# MegaShieldDB.net
KiCad netlist of a schematic drawn in EAGLE
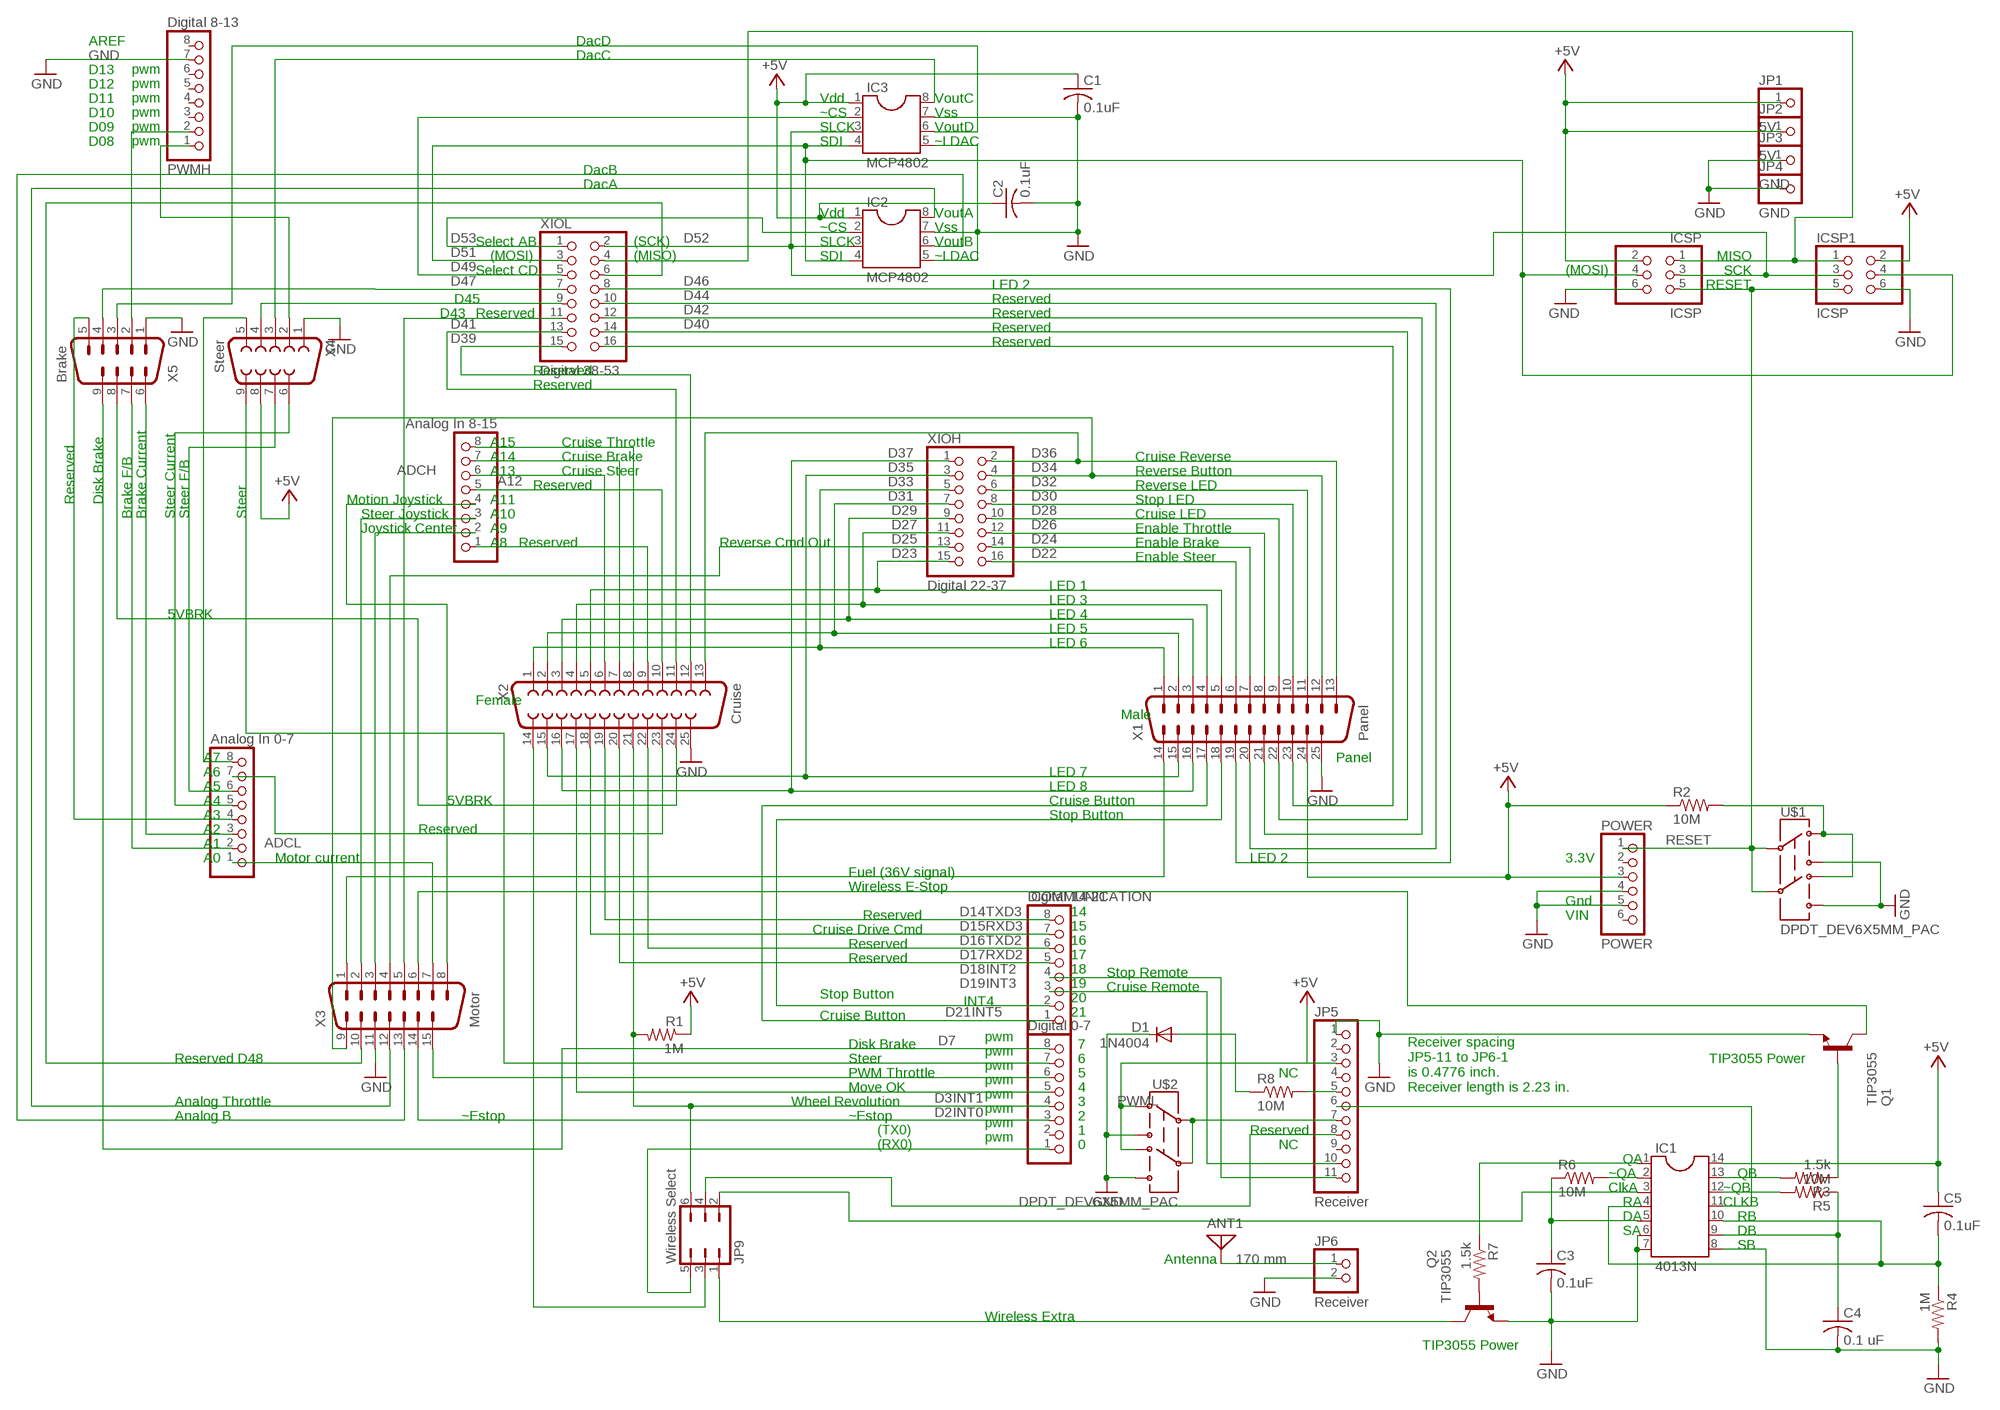
[diagram p0: schematic, sheet 1]

(export (version "E")
  (design (tool "Eeschema 10.0.6"))
  (components
    (comp (ref "ADCH")
      (value "Analog In 8-15")
      (footprint "eagle-import:1X08")
      (libsource (lib "eagle-import") (part "PINHD-1X8"))
    )
    (comp (ref "ADCL")
      (value "Analog In 0-7")
      (footprint "eagle-import:1X08")
      (libsource (lib "eagle-import") (part "PINHD-1X8"))
    )
    (comp (ref "ANT1")
      (value "170 mm")
      (footprint "eagle-import:PAD-01")
      (libsource (lib "eagle-import") (part "ANTENNA"))
    )
    (comp (ref "C1")
      (value "0.1uF")
      (footprint "eagle-import:C025-025X050")
      (libsource (lib "eagle-import") (part "C-US025-025X050"))
    )
    (comp (ref "C2")
      (value "0.1uF")
      (footprint "eagle-import:C025-025X050")
      (libsource (lib "eagle-import") (part "C-US025-025X050"))
    )
    (comp (ref "C3")
      (value "0.1uF")
      (footprint "eagle-import:C025-025X050")
      (libsource (lib "eagle-import") (part "C-US025-025X050"))
    )
    (comp (ref "C4")
      (value "0.1 uF")
      (footprint "eagle-import:C025-025X050")
      (libsource (lib "eagle-import") (part "C-US025-025X050"))
    )
    (comp (ref "C5")
      (value "0.1uF")
      (footprint "eagle-import:C025-025X050")
      (libsource (lib "eagle-import") (part "C-US025-025X050"))
    )
    (comp (ref "COMMUNICATION")
      (value "Digital 14-21")
      (footprint "eagle-import:1X08")
      (libsource (lib "eagle-import") (part "PINHD-1X8"))
    )
    (comp (ref "D1")
      (value "1N4004")
      (footprint "eagle-import:DO41-10")
      (libsource (lib "eagle-import") (part "1N4004"))
    )
    (comp (ref "IC1")
      (value "4013N")
      (footprint "eagle-import:DIL14")
      (libsource (lib "eagle-import") (part "DIL14"))
    )
    (comp (ref "IC2")
      (value "MCP4802")
      (footprint "eagle-import:DIL08")
      (libsource (lib "eagle-import") (part "DIL8"))
    )
    (comp (ref "IC3")
      (value "MCP4802")
      (footprint "eagle-import:DIL08")
      (libsource (lib "eagle-import") (part "DIL8"))
    )
    (comp (ref "ICSP")
      (value "ICSP")
      (footprint "eagle-import:2X03")
      (libsource (lib "eagle-import") (part "PINHD-2X3"))
    )
    (comp (ref "ICSP1")
      (value "ICSP")
      (footprint "eagle-import:2X03")
      (libsource (lib "eagle-import") (part "PINHD-2X3"))
    )
    (comp (ref "JP1")
      (value "5V")
      (footprint "eagle-import:1X01")
      (libsource (lib "eagle-import") (part "PINHD-1X1"))
    )
    (comp (ref "JP2")
      (value "5V")
      (footprint "eagle-import:1X01")
      (libsource (lib "eagle-import") (part "PINHD-1X1"))
    )
    (comp (ref "JP3")
      (value "GND")
      (footprint "eagle-import:1X01")
      (libsource (lib "eagle-import") (part "PINHD-1X1"))
    )
    (comp (ref "JP4")
      (value "GND")
      (footprint "eagle-import:1X01")
      (libsource (lib "eagle-import") (part "PINHD-1X1"))
    )
    (comp (ref "JP5")
      (value "Receiver")
      (footprint "eagle-import:1X11")
      (libsource (lib "eagle-import") (part "PINHD-1X11"))
    )
    (comp (ref "JP6")
      (value "Receiver")
      (footprint "eagle-import:1X02")
      (libsource (lib "eagle-import") (part "PINHD-1X2"))
    )
    (comp (ref "JP9")
      (value "Wireless Select")
      (footprint "eagle-import:JP3Q")
      (libsource (lib "eagle-import") (part "JP3Q"))
    )
    (comp (ref "POWER")
      (value "POWER")
      (footprint "eagle-import:1X06")
      (libsource (lib "eagle-import") (part "PINHD-1X6"))
    )
    (comp (ref "PWMH")
      (value "Digital 8-13")
      (footprint "eagle-import:1X08")
      (libsource (lib "eagle-import") (part "PINHD-1X8"))
    )
    (comp (ref "PWML")
      (value "Digital 0-7")
      (footprint "eagle-import:1X08")
      (libsource (lib "eagle-import") (part "PINHD-1X8"))
    )
    (comp (ref "Q1")
      (value "TIP3055")
      (footprint "eagle-import:TO220")
      (libsource (lib "eagle-import") (part "BD239"))
    )
    (comp (ref "Q2")
      (value "TIP3055")
      (footprint "eagle-import:TO220")
      (libsource (lib "eagle-import") (part "BD239"))
    )
    (comp (ref "R1")
      (value "1M")
      (footprint "eagle-import:0204_5")
      (libsource (lib "eagle-import") (part "R-US_0204/5"))
    )
    (comp (ref "R2")
      (value "10M")
      (footprint "eagle-import:0204_5")
      (libsource (lib "eagle-import") (part "R-US_0204/5"))
    )
    (comp (ref "R3")
      (value "1.5k")
      (footprint "eagle-import:0204_5")
      (libsource (lib "eagle-import") (part "R-US_0204/5"))
    )
    (comp (ref "R4")
      (value "1M")
      (footprint "eagle-import:0204_5")
      (libsource (lib "eagle-import") (part "R-US_0204/5"))
    )
    (comp (ref "R5")
      (value "10M")
      (footprint "eagle-import:0204_5")
      (libsource (lib "eagle-import") (part "R-US_0204/5"))
    )
    (comp (ref "R6")
      (value "10M")
      (footprint "eagle-import:0204_5")
      (libsource (lib "eagle-import") (part "R-US_0204/5"))
    )
    (comp (ref "R7")
      (value "1.5k")
      (footprint "eagle-import:0204_5")
      (libsource (lib "eagle-import") (part "R-US_0204/5"))
    )
    (comp (ref "R8")
      (value "10M")
      (footprint "eagle-import:0204_5")
      (libsource (lib "eagle-import") (part "R-US_0204/5"))
    )
    (comp (ref "U$1")
      (value "DPDT_DEV6X5MM_PAC")
      (footprint "eagle-import:NEWSWITCH2_PAC")
      (libsource (lib "eagle-import") (part "DPDT_DEV6X5MM_PAC"))
    )
    (comp (ref "U$2")
      (value "DPDT_DEV6X5MM_PAC")
      (footprint "eagle-import:NEWSWITCH2_PAC")
      (libsource (lib "eagle-import") (part "DPDT_DEV6X5MM_PAC"))
    )
    (comp (ref "X1")
      (value "Panel")
      (footprint "eagle-import:M25-HD-20")
      (libsource (lib "eagle-import") (part "M25-HD-20"))
    )
    (comp (ref "X2")
      (value "Cruise")
      (footprint "eagle-import:F25H")
      (libsource (lib "eagle-import") (part "F25H"))
    )
    (comp (ref "X3")
      (value "Motor")
      (footprint "eagle-import:182-015-MALE")
      (libsource (lib "eagle-import") (part "M15-182"))
    )
    (comp (ref "X4")
      (value "Steer")
      (footprint "eagle-import:F09H")
      (libsource (lib "eagle-import") (part "F09H"))
    )
    (comp (ref "X5")
      (value "Brake")
      (footprint "eagle-import:182-009-MALE")
      (libsource (lib "eagle-import") (part "M09-182"))
    )
    (comp (ref "XIOH")
      (value "Digital 22-37")
      (footprint "eagle-import:2X08")
      (libsource (lib "eagle-import") (part "PINHD-2X8"))
    )
    (comp (ref "XIOL")
      (value "Digital 38-53")
      (footprint "eagle-import:2X08")
      (libsource (lib "eagle-import") (part "PINHD-2X8"))
    )
  )
  (nets
    (net (code "1") (name "+5V") (class "Default")
      (node (ref "C1") (pin "1") (pinfunction "1_1") (pintype "passive"))
      (node (ref "C2") (pin "1") (pinfunction "1_1") (pintype "passive"))
      (node (ref "C5") (pin "1") (pinfunction "1_1") (pintype "passive"))
      (node (ref "IC1") (pin "14") (pinfunction "14_14") (pintype "passive"))
      (node (ref "IC2") (pin "1") (pinfunction "1_1") (pintype "passive"))
      (node (ref "IC3") (pin "1") (pinfunction "1_1") (pintype "passive"))
      (node (ref "ICSP") (pin "2") (pinfunction "2_2") (pintype "passive"))
      (node (ref "ICSP1") (pin "2") (pinfunction "2_2") (pintype "passive"))
      (node (ref "JP1") (pin "1") (pinfunction "1_1") (pintype "passive"))
      (node (ref "JP2") (pin "1") (pinfunction "1_1") (pintype "passive"))
      (node (ref "JP5") (pin "3") (pinfunction "3_3") (pintype "passive"))
      (node (ref "POWER") (pin "3") (pinfunction "3_3") (pintype "passive"))
      (node (ref "R1") (pin "1") (pinfunction "1_1") (pintype "passive"))
      (node (ref "R2") (pin "1") (pinfunction "1_1") (pintype "passive"))
      (node (ref "U$2") (pin "PIN1") (pinfunction "1_PIN1") (pintype "bidirectional"))
      (node (ref "U$2") (pin "PIN4") (pinfunction "4_PIN4") (pintype "bidirectional"))
      (node (ref "X1") (pin "24") (pinfunction "24_24") (pintype "passive"))
      (node (ref "X4") (pin "8") (pinfunction "8_8") (pintype "passive"))
    )
    (net (code "2") (name "/A12") (class "Default")
      (node (ref "ADCH") (pin "5") (pinfunction "5_5") (pintype "passive"))
      (node (ref "X2") (pin "10") (pinfunction "10_10") (pintype "passive"))
    )
    (net (code "3") (name "/D2INT0") (class "Default")
      (node (ref "PWML") (pin "3") (pinfunction "3_3") (pintype "passive"))
      (node (ref "X3") (pin "14") (pinfunction "14_14") (pintype "passive"))
    )
    (net (code "4") (name "/D3INT1") (class "Default")
      (node (ref "JP9") (pin "6") (pinfunction "6_6") (pintype "passive"))
      (node (ref "PWML") (pin "4") (pinfunction "4_4") (pintype "passive"))
      (node (ref "R1") (pin "2") (pinfunction "2_2") (pintype "passive"))
      (node (ref "X2") (pin "21") (pinfunction "21_21") (pintype "passive"))
    )
    (net (code "5") (name "/D7") (class "Default")
      (node (ref "PWML") (pin "8") (pinfunction "8_8") (pintype "passive"))
      (node (ref "X5") (pin "9") (pinfunction "9_9") (pintype "passive"))
    )
    (net (code "6") (name "/D14TXD3") (class "Default")
      (node (ref "COMMUNICATION") (pin "8") (pinfunction "8_8") (pintype "passive"))
      (node (ref "X2") (pin "19") (pinfunction "19_19") (pintype "passive"))
    )
    (net (code "7") (name "/D15RXD3") (class "Default")
      (node (ref "COMMUNICATION") (pin "7") (pinfunction "7_7") (pintype "passive"))
      (node (ref "X2") (pin "18") (pinfunction "18_18") (pintype "passive"))
    )
    (net (code "8") (name "/D16TXD2") (class "Default")
      (node (ref "COMMUNICATION") (pin "6") (pinfunction "6_6") (pintype "passive"))
      (node (ref "X2") (pin "22") (pinfunction "22_22") (pintype "passive"))
    )
    (net (code "9") (name "/D17RXD2") (class "Default")
      (node (ref "COMMUNICATION") (pin "5") (pinfunction "5_5") (pintype "passive"))
      (node (ref "X2") (pin "20") (pinfunction "20_20") (pintype "passive"))
    )
    (net (code "10") (name "/D18INT2") (class "Default")
      (node (ref "COMMUNICATION") (pin "4") (pinfunction "4_4") (pintype "passive"))
      (node (ref "JP5") (pin "11") (pinfunction "11_11") (pintype "passive"))
    )
    (net (code "11") (name "/D19INT3") (class "Default")
      (node (ref "COMMUNICATION") (pin "3") (pinfunction "3_3") (pintype "passive"))
      (node (ref "JP5") (pin "10") (pinfunction "10_10") (pintype "passive"))
    )
    (net (code "12") (name "/D21INT5") (class "Default")
      (node (ref "COMMUNICATION") (pin "1") (pinfunction "1_1") (pintype "passive"))
      (node (ref "X1") (pin "17") (pinfunction "17_17") (pintype "passive"))
    )
    (net (code "13") (name "/D22") (class "Default")
      (node (ref "X1") (pin "6") (pinfunction "6_6") (pintype "passive"))
      (node (ref "XIOH") (pin "16") (pinfunction "16_16") (pintype "passive"))
    )
    (net (code "14") (name "/D23") (class "Default")
      (node (ref "X1") (pin "5") (pinfunction "5_5") (pintype "passive"))
      (node (ref "X2") (pin "5") (pinfunction "5_5") (pintype "passive"))
      (node (ref "XIOH") (pin "15") (pinfunction "15_15") (pintype "passive"))
    )
    (net (code "15") (name "/D24") (class "Default")
      (node (ref "X1") (pin "7") (pinfunction "7_7") (pintype "passive"))
      (node (ref "XIOH") (pin "14") (pinfunction "14_14") (pintype "passive"))
    )
    (net (code "16") (name "/D25") (class "Default")
      (node (ref "X3") (pin "4") (pinfunction "4_4") (pintype "passive"))
      (node (ref "XIOH") (pin "13") (pinfunction "13_13") (pintype "passive"))
    )
    (net (code "17") (name "/D26") (class "Default")
      (node (ref "X1") (pin "8") (pinfunction "8_8") (pintype "passive"))
      (node (ref "XIOH") (pin "12") (pinfunction "12_12") (pintype "passive"))
    )
    (net (code "18") (name "/D27") (class "Default")
      (node (ref "X1") (pin "4") (pinfunction "4_4") (pintype "passive"))
      (node (ref "X2") (pin "4") (pinfunction "4_4") (pintype "passive"))
      (node (ref "XIOH") (pin "11") (pinfunction "11_11") (pintype "passive"))
    )
    (net (code "19") (name "/D28") (class "Default")
      (node (ref "X1") (pin "9") (pinfunction "9_9") (pintype "passive"))
      (node (ref "XIOH") (pin "10") (pinfunction "10_10") (pintype "passive"))
    )
    (net (code "20") (name "/D29") (class "Default")
      (node (ref "X1") (pin "3") (pinfunction "3_3") (pintype "passive"))
      (node (ref "X2") (pin "3") (pinfunction "3_3") (pintype "passive"))
      (node (ref "XIOH") (pin "9") (pinfunction "9_9") (pintype "passive"))
    )
    (net (code "21") (name "/D30") (class "Default")
      (node (ref "X1") (pin "10") (pinfunction "10_10") (pintype "passive"))
      (node (ref "XIOH") (pin "8") (pinfunction "8_8") (pintype "passive"))
    )
    (net (code "22") (name "/D31") (class "Default")
      (node (ref "X1") (pin "2") (pinfunction "2_2") (pintype "passive"))
      (node (ref "X2") (pin "2") (pinfunction "2_2") (pintype "passive"))
      (node (ref "XIOH") (pin "7") (pinfunction "7_7") (pintype "passive"))
    )
    (net (code "23") (name "/D32") (class "Default")
      (node (ref "X1") (pin "11") (pinfunction "11_11") (pintype "passive"))
      (node (ref "XIOH") (pin "6") (pinfunction "6_6") (pintype "passive"))
    )
    (net (code "24") (name "/D33") (class "Default")
      (node (ref "X1") (pin "1") (pinfunction "1_1") (pintype "passive"))
      (node (ref "X2") (pin "1") (pinfunction "1_1") (pintype "passive"))
      (node (ref "XIOH") (pin "5") (pinfunction "5_5") (pintype "passive"))
    )
    (net (code "25") (name "/D34") (class "Default")
      (node (ref "X1") (pin "12") (pinfunction "12_12") (pintype "passive"))
      (node (ref "X3") (pin "9") (pinfunction "9_9") (pintype "passive"))
      (node (ref "XIOH") (pin "4") (pinfunction "4_4") (pintype "passive"))
    )
    (net (code "26") (name "/D35") (class "Default")
      (node (ref "X1") (pin "15") (pinfunction "15_15") (pintype "passive"))
      (node (ref "X2") (pin "15") (pinfunction "15_15") (pintype "passive"))
      (node (ref "XIOH") (pin "3") (pinfunction "3_3") (pintype "passive"))
    )
    (net (code "27") (name "/D36") (class "Default")
      (node (ref "X1") (pin "13") (pinfunction "13_13") (pintype "passive"))
      (node (ref "X2") (pin "13") (pinfunction "13_13") (pintype "passive"))
      (node (ref "XIOH") (pin "2") (pinfunction "2_2") (pintype "passive"))
    )
    (net (code "28") (name "/D37") (class "Default")
      (node (ref "X1") (pin "16") (pinfunction "16_16") (pintype "passive"))
      (node (ref "X2") (pin "16") (pinfunction "16_16") (pintype "passive"))
      (node (ref "XIOH") (pin "1") (pinfunction "1_1") (pintype "passive"))
    )
    (net (code "29") (name "/D39") (class "Default")
      (node (ref "X2") (pin "12") (pinfunction "12_12") (pintype "passive"))
      (node (ref "XIOL") (pin "15") (pinfunction "15_15") (pintype "passive"))
    )
    (net (code "30") (name "/D40") (class "Default")
      (node (ref "X1") (pin "22") (pinfunction "22_22") (pintype "passive"))
      (node (ref "XIOL") (pin "14") (pinfunction "14_14") (pintype "passive"))
    )
    (net (code "31") (name "/D41") (class "Default")
      (node (ref "X2") (pin "11") (pinfunction "11_11") (pintype "passive"))
      (node (ref "XIOL") (pin "13") (pinfunction "13_13") (pintype "passive"))
    )
    (net (code "32") (name "/D42") (class "Default")
      (node (ref "X1") (pin "21") (pinfunction "21_21") (pintype "passive"))
      (node (ref "XIOL") (pin "12") (pinfunction "12_12") (pintype "passive"))
    )
    (net (code "33") (name "/D44") (class "Default")
      (node (ref "X1") (pin "20") (pinfunction "20_20") (pintype "passive"))
      (node (ref "XIOL") (pin "10") (pinfunction "10_10") (pintype "passive"))
    )
    (net (code "34") (name "/D46") (class "Default")
      (node (ref "X1") (pin "19") (pinfunction "19_19") (pintype "passive"))
      (node (ref "XIOL") (pin "8") (pinfunction "8_8") (pintype "passive"))
    )
    (net (code "35") (name "/D47") (class "Default")
      (node (ref "X5") (pin "4") (pinfunction "4_4") (pintype "passive"))
      (node (ref "XIOL") (pin "7") (pinfunction "7_7") (pintype "passive"))
    )
    (net (code "36") (name "/D49") (class "Default")
      (node (ref "IC3") (pin "2") (pinfunction "2_2") (pintype "passive"))
      (node (ref "XIOL") (pin "5") (pinfunction "5_5") (pintype "passive"))
    )
    (net (code "37") (name "/D51") (class "Default")
      (node (ref "IC2") (pin "4") (pinfunction "4_4") (pintype "passive"))
      (node (ref "IC3") (pin "4") (pinfunction "4_4") (pintype "passive"))
      (node (ref "ICSP") (pin "4") (pinfunction "4_4") (pintype "passive"))
      (node (ref "ICSP1") (pin "4") (pinfunction "4_4") (pintype "passive"))
      (node (ref "XIOL") (pin "3") (pinfunction "3_3") (pintype "passive"))
    )
    (net (code "38") (name "/D52") (class "Default")
      (node (ref "IC2") (pin "3") (pinfunction "3_3") (pintype "passive"))
      (node (ref "IC3") (pin "3") (pinfunction "3_3") (pintype "passive"))
      (node (ref "ICSP") (pin "3") (pinfunction "3_3") (pintype "passive"))
      (node (ref "ICSP1") (pin "3") (pinfunction "3_3") (pintype "passive"))
      (node (ref "XIOL") (pin "2") (pinfunction "2_2") (pintype "passive"))
    )
    (net (code "39") (name "/D53") (class "Default")
      (node (ref "IC2") (pin "2") (pinfunction "2_2") (pintype "passive"))
      (node (ref "XIOL") (pin "1") (pinfunction "1_1") (pintype "passive"))
    )
    (net (code "40") (name "/RESET") (class "Default")
      (node (ref "ICSP") (pin "5") (pinfunction "5_5") (pintype "passive"))
      (node (ref "ICSP1") (pin "5") (pinfunction "5_5") (pintype "passive"))
      (node (ref "POWER") (pin "1") (pinfunction "1_1") (pintype "passive"))
      (node (ref "U$1") (pin "PIN2") (pinfunction "2_PIN2") (pintype "bidirectional"))
      (node (ref "U$1") (pin "PIN5") (pinfunction "5_PIN5") (pintype "bidirectional"))
    )
    (net (code "41") (name "GND") (class "Default")
      (node (ref "C1") (pin "2") (pinfunction "2_2") (pintype "passive"))
      (node (ref "C2") (pin "2") (pinfunction "2_2") (pintype "passive"))
      (node (ref "C3") (pin "2") (pinfunction "2_2") (pintype "passive"))
      (node (ref "C4") (pin "2") (pinfunction "2_2") (pintype "passive"))
      (node (ref "D1") (pin "C") (pinfunction "C_C") (pintype "passive"))
      (node (ref "IC1") (pin "6") (pinfunction "6_6") (pintype "passive"))
      (node (ref "IC1") (pin "7") (pinfunction "7_7") (pintype "passive"))
      (node (ref "IC1") (pin "8") (pinfunction "8_8") (pintype "passive"))
      (node (ref "IC2") (pin "5") (pinfunction "5_5") (pintype "passive"))
      (node (ref "IC2") (pin "7") (pinfunction "7_7") (pintype "passive"))
      (node (ref "IC3") (pin "5") (pinfunction "5_5") (pintype "passive"))
      (node (ref "IC3") (pin "7") (pinfunction "7_7") (pintype "passive"))
      (node (ref "ICSP") (pin "6") (pinfunction "6_6") (pintype "passive"))
      (node (ref "ICSP1") (pin "6") (pinfunction "6_6") (pintype "passive"))
      (node (ref "JP3") (pin "1") (pinfunction "1_1") (pintype "passive"))
      (node (ref "JP4") (pin "1") (pinfunction "1_1") (pintype "passive"))
      (node (ref "JP5") (pin "1") (pinfunction "1_1") (pintype "passive"))
      (node (ref "JP6") (pin "2") (pinfunction "2_2") (pintype "passive"))
      (node (ref "POWER") (pin "4") (pinfunction "4_4") (pintype "passive"))
      (node (ref "POWER") (pin "5") (pinfunction "5_5") (pintype "passive"))
      (node (ref "PWMH") (pin "7") (pinfunction "7_7") (pintype "passive"))
      (node (ref "Q1") (pin "3") (pinfunction "E_3") (pintype "passive"))
      (node (ref "Q2") (pin "3") (pinfunction "E_3") (pintype "passive"))
      (node (ref "R4") (pin "2") (pinfunction "2_2") (pintype "passive"))
      (node (ref "U$1") (pin "PIN3") (pinfunction "3_PIN3") (pintype "bidirectional"))
      (node (ref "U$1") (pin "PIN6") (pinfunction "6_PIN6") (pintype "bidirectional"))
      (node (ref "U$2") (pin "PIN3") (pinfunction "3_PIN3") (pintype "bidirectional"))
      (node (ref "U$2") (pin "PIN6") (pinfunction "6_PIN6") (pintype "bidirectional"))
      (node (ref "X1") (pin "25") (pinfunction "25_25") (pintype "passive"))
      (node (ref "X2") (pin "25") (pinfunction "25_25") (pintype "passive"))
      (node (ref "X3") (pin "11") (pinfunction "11_11") (pintype "passive"))
      (node (ref "X4") (pin "1") (pinfunction "1_1") (pintype "passive"))
      (node (ref "X5") (pin "1") (pinfunction "1_1") (pintype "passive"))
    )
    (net (code "42") (name "Net-(ADCH-Pad1)") (class "Default")
      (node (ref "ADCH") (pin "1") (pinfunction "1_1") (pintype "passive"))
      (node (ref "X2") (pin "9") (pinfunction "9_9") (pintype "passive"))
    )
    (net (code "43") (name "Net-(ADCH-Pad2)") (class "Default")
      (node (ref "ADCH") (pin "2") (pinfunction "2_2") (pintype "passive"))
      (node (ref "X3") (pin "3") (pinfunction "3_3") (pintype "passive"))
    )
    (net (code "44") (name "Net-(ADCH-Pad3)") (class "Default")
      (node (ref "ADCH") (pin "3") (pinfunction "3_3") (pintype "passive"))
      (node (ref "X3") (pin "2") (pinfunction "2_2") (pintype "passive"))
    )
    (net (code "45") (name "Net-(ADCH-Pad4)") (class "Default")
      (node (ref "ADCH") (pin "4") (pinfunction "4_4") (pintype "passive"))
      (node (ref "X3") (pin "8") (pinfunction "8_8") (pintype "passive"))
    )
    (net (code "46") (name "Net-(ADCH-Pad6)") (class "Default")
      (node (ref "ADCH") (pin "6") (pinfunction "6_6") (pintype "passive"))
      (node (ref "X2") (pin "6") (pinfunction "6_6") (pintype "passive"))
    )
    (net (code "47") (name "Net-(ADCH-Pad7)") (class "Default")
      (node (ref "ADCH") (pin "7") (pinfunction "7_7") (pintype "passive"))
      (node (ref "X2") (pin "7") (pinfunction "7_7") (pintype "passive"))
    )
    (net (code "48") (name "Net-(ADCH-Pad8)") (class "Default")
      (node (ref "ADCH") (pin "8") (pinfunction "8_8") (pintype "passive"))
      (node (ref "X2") (pin "8") (pinfunction "8_8") (pintype "passive"))
    )
    (net (code "49") (name "Net-(ADCL-Pad1)") (class "Default")
      (node (ref "ADCL") (pin "1") (pinfunction "1_1") (pintype "passive"))
      (node (ref "X3") (pin "7") (pinfunction "7_7") (pintype "passive"))
    )
    (net (code "50") (name "Net-(ADCL-Pad2)") (class "Default")
      (node (ref "ADCL") (pin "2") (pinfunction "2_2") (pintype "passive"))
      (node (ref "X5") (pin "7") (pinfunction "7_7") (pintype "passive"))
    )
    (net (code "51") (name "Net-(ADCL-Pad3)") (class "Default")
      (node (ref "ADCL") (pin "3") (pinfunction "3_3") (pintype "passive"))
      (node (ref "X5") (pin "6") (pinfunction "6_6") (pintype "passive"))
    )
    (net (code "52") (name "Net-(ADCL-Pad4)") (class "Default")
      (node (ref "ADCL") (pin "4") (pinfunction "4_4") (pintype "passive"))
      (node (ref "X5") (pin "5") (pinfunction "5_5") (pintype "passive"))
    )
    (net (code "53") (name "Net-(ADCL-Pad5)") (class "Default")
      (node (ref "ADCL") (pin "5") (pinfunction "5_5") (pintype "passive"))
      (node (ref "X4") (pin "6") (pinfunction "6_6") (pintype "passive"))
    )
    (net (code "54") (name "Net-(ADCL-Pad6)") (class "Default")
      (node (ref "ADCL") (pin "6") (pinfunction "6_6") (pintype "passive"))
      (node (ref "X4") (pin "7") (pinfunction "7_7") (pintype "passive"))
    )
    (net (code "55") (name "Net-(ADCL-Pad7)") (class "Default")
      (node (ref "ADCL") (pin "7") (pinfunction "7_7") (pintype "passive"))
      (node (ref "X2") (pin "23") (pinfunction "23_23") (pintype "passive"))
    )
    (net (code "56") (name "Net-(ADCL-Pad8)") (class "Default")
      (node (ref "ADCL") (pin "8") (pinfunction "8_8") (pintype "passive"))
      (node (ref "X4") (pin "5") (pinfunction "5_5") (pintype "passive"))
    )
    (net (code "57") (name "Net-(ANT1-Pad1)") (class "Default")
      (node (ref "ANT1") (pin "1") (pinfunction "1_1") (pintype "output"))
      (node (ref "JP6") (pin "1") (pinfunction "1_1") (pintype "passive"))
    )
    (net (code "58") (name "Net-(C3-Pad1)") (class "Default")
      (node (ref "C3") (pin "1") (pinfunction "1_1") (pintype "passive"))
      (node (ref "IC1") (pin "5") (pinfunction "5_5") (pintype "passive"))
      (node (ref "R6") (pin "1") (pinfunction "1_1") (pintype "passive"))
    )
    (net (code "59") (name "Net-(C4-Pad1)") (class "Default")
      (node (ref "C4") (pin "1") (pinfunction "1_1") (pintype "passive"))
      (node (ref "IC1") (pin "9") (pinfunction "9_9") (pintype "passive"))
      (node (ref "R5") (pin "1") (pinfunction "1_1") (pintype "passive"))
    )
    (net (code "60") (name "Net-(C5-Pad2)") (class "Default")
      (node (ref "C5") (pin "2") (pinfunction "2_2") (pintype "passive"))
      (node (ref "IC1") (pin "10") (pinfunction "10_10") (pintype "passive"))
      (node (ref "IC1") (pin "4") (pinfunction "4_4") (pintype "passive"))
      (node (ref "R4") (pin "1") (pinfunction "1_1") (pintype "passive"))
    )
    (net (code "61") (name "Net-(COMMUNICATION-Pad2)") (class "Default")
      (node (ref "COMMUNICATION") (pin "2") (pinfunction "2_2") (pintype "passive"))
      (node (ref "X1") (pin "18") (pinfunction "18_18") (pintype "passive"))
    )
    (net (code "62") (name "Net-(D1-PadA)") (class "Default")
      (node (ref "D1") (pin "A") (pinfunction "A_A") (pintype "passive"))
      (node (ref "R8") (pin "1") (pinfunction "1_1") (pintype "passive"))
    )
    (net (code "63") (name "Net-(IC1-Pad1)") (class "Default")
      (node (ref "IC1") (pin "1") (pinfunction "1_1") (pintype "passive"))
      (node (ref "R7") (pin "1") (pinfunction "1_1") (pintype "passive"))
    )
    (net (code "64") (name "Net-(IC1-Pad2)") (class "Default")
      (node (ref "IC1") (pin "2") (pinfunction "2_2") (pintype "passive"))
      (node (ref "R6") (pin "2") (pinfunction "2_2") (pintype "passive"))
    )
    (net (code "65") (name "Net-(IC1-Pad3)") (class "Default")
      (node (ref "IC1") (pin "3") (pinfunction "3_3") (pintype "passive"))
      (node (ref "JP9") (pin "2") (pinfunction "2_2") (pintype "passive"))
    )
    (net (code "66") (name "Net-(IC1-Pad11)") (class "Default")
      (node (ref "IC1") (pin "11") (pinfunction "11_11") (pintype "passive"))
      (node (ref "JP5") (pin "6") (pinfunction "6_6") (pintype "passive"))
    )
    (net (code "67") (name "Net-(IC1-Pad12)") (class "Default")
      (node (ref "IC1") (pin "12") (pinfunction "12_12") (pintype "passive"))
      (node (ref "R5") (pin "2") (pinfunction "2_2") (pintype "passive"))
    )
    (net (code "68") (name "Net-(IC1-Pad13)") (class "Default")
      (node (ref "IC1") (pin "13") (pinfunction "13_13") (pintype "passive"))
      (node (ref "R3") (pin "2") (pinfunction "2_2") (pintype "passive"))
    )
    (net (code "69") (name "Net-(IC2-Pad6)") (class "Default")
      (node (ref "IC2") (pin "6") (pinfunction "6_6") (pintype "passive"))
      (node (ref "X3") (pin "13") (pinfunction "13_13") (pintype "passive"))
    )
    (net (code "70") (name "Net-(IC2-Pad8)") (class "Default")
      (node (ref "IC2") (pin "8") (pinfunction "8_8") (pintype "passive"))
      (node (ref "X3") (pin "12") (pinfunction "12_12") (pintype "passive"))
    )
    (net (code "71") (name "Net-(IC3-Pad6)") (class "Default")
      (node (ref "IC3") (pin "6") (pinfunction "6_6") (pintype "passive"))
      (node (ref "X5") (pin "3") (pinfunction "3_3") (pintype "passive"))
    )
    (net (code "72") (name "Net-(IC3-Pad8)") (class "Default")
      (node (ref "IC3") (pin "8") (pinfunction "8_8") (pintype "passive"))
      (node (ref "X4") (pin "3") (pinfunction "3_3") (pintype "passive"))
    )
    (net (code "73") (name "Net-(ICSP-Pad1)") (class "Default")
      (node (ref "ICSP") (pin "1") (pinfunction "1_1") (pintype "passive"))
      (node (ref "ICSP1") (pin "1") (pinfunction "1_1") (pintype "passive"))
      (node (ref "XIOL") (pin "4") (pinfunction "4_4") (pintype "passive"))
    )
    (net (code "74") (name "Net-(JP5-Pad5)") (class "Default")
      (node (ref "JP5") (pin "5") (pinfunction "5_5") (pintype "passive"))
      (node (ref "R8") (pin "2") (pinfunction "2_2") (pintype "passive"))
    )
    (net (code "75") (name "Net-(JP5-Pad8)") (class "Default")
      (node (ref "JP5") (pin "8") (pinfunction "8_8") (pintype "passive"))
      (node (ref "JP9") (pin "4") (pinfunction "4_4") (pintype "passive"))
    )
    (net (code "76") (name "Net-(JP9-Pad3)") (class "Default")
      (node (ref "JP9") (pin "3") (pinfunction "3_3") (pintype "passive"))
      (node (ref "X2") (pin "14") (pinfunction "14_14") (pintype "passive"))
    )
    (net (code "77") (name "Net-(JP9-Pad5)") (class "Default")
      (node (ref "JP9") (pin "5") (pinfunction "5_5") (pintype "passive"))
      (node (ref "PWML") (pin "1") (pinfunction "1_1") (pintype "passive"))
    )
    (net (code "78") (name "Net-(PWMH-Pad1)") (class "Default")
      (node (ref "PWMH") (pin "1") (pinfunction "1_1") (pintype "passive"))
      (node (ref "X4") (pin "2") (pinfunction "2_2") (pintype "passive"))
    )
    (net (code "79") (name "Net-(PWMH-Pad2)") (class "Default")
      (node (ref "PWMH") (pin "2") (pinfunction "2_2") (pintype "passive"))
      (node (ref "X5") (pin "2") (pinfunction "2_2") (pintype "passive"))
    )
    (net (code "80") (name "Net-(PWML-Pad5)") (class "Default")
      (node (ref "PWML") (pin "5") (pinfunction "5_5") (pintype "passive"))
      (node (ref "X2") (pin "17") (pinfunction "17_17") (pintype "passive"))
    )
    (net (code "81") (name "Net-(PWML-Pad6)") (class "Default")
      (node (ref "PWML") (pin "6") (pinfunction "6_6") (pintype "passive"))
      (node (ref "X3") (pin "15") (pinfunction "15_15") (pintype "passive"))
    )
    (net (code "82") (name "Net-(PWML-Pad7)") (class "Default")
      (node (ref "PWML") (pin "7") (pinfunction "7_7") (pintype "passive"))
      (node (ref "X4") (pin "9") (pinfunction "9_9") (pintype "passive"))
    )
    (net (code "83") (name "Net-(Q1-B)") (class "Default")
      (node (ref "Q1") (pin "1") (pinfunction "B_1") (pintype "passive"))
      (node (ref "R3") (pin "1") (pinfunction "1_1") (pintype "passive"))
    )
    (net (code "84") (name "Net-(Q1-C)") (class "Default")
      (node (ref "Q1") (pin "2") (pinfunction "C_2") (pintype "passive"))
      (node (ref "X3") (pin "6") (pinfunction "6_6") (pintype "passive"))
    )
    (net (code "85") (name "Net-(Q2-B)") (class "Default")
      (node (ref "Q2") (pin "1") (pinfunction "B_1") (pintype "passive"))
      (node (ref "R7") (pin "2") (pinfunction "2_2") (pintype "passive"))
    )
    (net (code "86") (name "Net-(Q2-C)") (class "Default")
      (node (ref "JP9") (pin "1") (pinfunction "1_1") (pintype "passive"))
      (node (ref "Q2") (pin "2") (pinfunction "C_2") (pintype "passive"))
    )
    (net (code "87") (name "Net-(U$1-1)") (class "Default")
      (node (ref "R2") (pin "2") (pinfunction "2_2") (pintype "passive"))
      (node (ref "U$1") (pin "PIN1") (pinfunction "1_PIN1") (pintype "bidirectional"))
      (node (ref "U$1") (pin "PIN4") (pinfunction "4_PIN4") (pintype "bidirectional"))
    )
    (net (code "88") (name "Net-(U$2-2)") (class "Default")
      (node (ref "JP5") (pin "7") (pinfunction "7_7") (pintype "passive"))
      (node (ref "U$2") (pin "PIN2") (pinfunction "2_PIN2") (pintype "bidirectional"))
      (node (ref "U$2") (pin "PIN5") (pinfunction "5_PIN5") (pintype "bidirectional"))
    )
    (net (code "89") (name "Net-(X1-Pad14)") (class "Default")
      (node (ref "X1") (pin "14") (pinfunction "14_14") (pintype "passive"))
      (node (ref "X3") (pin "1") (pinfunction "1_1") (pintype "passive"))
    )
    (net (code "90") (name "Net-(X1-Pad23)") (class "Default")
      (node (ref "X1") (pin "23") (pinfunction "23_23") (pintype "passive"))
      (node (ref "XIOL") (pin "16") (pinfunction "16_16") (pintype "passive"))
    )
    (net (code "91") (name "Net-(X2-Pad24)") (class "Default")
      (node (ref "X2") (pin "24") (pinfunction "24_24") (pintype "passive"))
      (node (ref "X5") (pin "8") (pinfunction "8_8") (pintype "passive"))
    )
    (net (code "92") (name "Net-(X3-Pad5)") (class "Default")
      (node (ref "X3") (pin "5") (pinfunction "5_5") (pintype "passive"))
      (node (ref "XIOL") (pin "11") (pinfunction "11_11") (pintype "passive"))
    )
    (net (code "93") (name "Net-(X3-Pad10)") (class "Default")
      (node (ref "X3") (pin "10") (pinfunction "10_10") (pintype "passive"))
      (node (ref "XIOL") (pin "6") (pinfunction "6_6") (pintype "passive"))
    )
    (net (code "94") (name "Net-(X4-Pad4)") (class "Default")
      (node (ref "X4") (pin "4") (pinfunction "4_4") (pintype "passive"))
      (node (ref "XIOL") (pin "9") (pinfunction "9_9") (pintype "passive"))
    )
    (net (code "95") (name "unconnected-(JP5-Pad2)") (class "Default")
      (node (ref "JP5") (pin "2") (pinfunction "2_2") (pintype "passive"))
    )
    (net (code "96") (name "unconnected-(JP5-Pad4)") (class "Default")
      (node (ref "JP5") (pin "4") (pinfunction "4_4") (pintype "passive"))
    )
    (net (code "97") (name "unconnected-(JP5-Pad9)") (class "Default")
      (node (ref "JP5") (pin "9") (pinfunction "9_9") (pintype "passive"))
    )
    (net (code "98") (name "unconnected-(POWER-Pad2)") (class "Default")
      (node (ref "POWER") (pin "2") (pinfunction "2_2") (pintype "passive"))
    )
    (net (code "99") (name "unconnected-(POWER-Pad6)") (class "Default")
      (node (ref "POWER") (pin "6") (pinfunction "6_6") (pintype "passive"))
    )
    (net (code "100") (name "unconnected-(PWMH-Pad3)") (class "Default")
      (node (ref "PWMH") (pin "3") (pinfunction "3_3") (pintype "passive"))
    )
    (net (code "101") (name "unconnected-(PWMH-Pad4)") (class "Default")
      (node (ref "PWMH") (pin "4") (pinfunction "4_4") (pintype "passive"))
    )
    (net (code "102") (name "unconnected-(PWMH-Pad5)") (class "Default")
      (node (ref "PWMH") (pin "5") (pinfunction "5_5") (pintype "passive"))
    )
    (net (code "103") (name "unconnected-(PWMH-Pad6)") (class "Default")
      (node (ref "PWMH") (pin "6") (pinfunction "6_6") (pintype "passive"))
    )
    (net (code "104") (name "unconnected-(PWMH-Pad8)") (class "Default")
      (node (ref "PWMH") (pin "8") (pinfunction "8_8") (pintype "passive"))
    )
    (net (code "105") (name "unconnected-(PWML-Pad2)") (class "Default")
      (node (ref "PWML") (pin "2") (pinfunction "2_2") (pintype "passive"))
    )
  )
)
